# 03_Template_Indication.net
KiCad netlist of a schematic drawn in Altium Designer
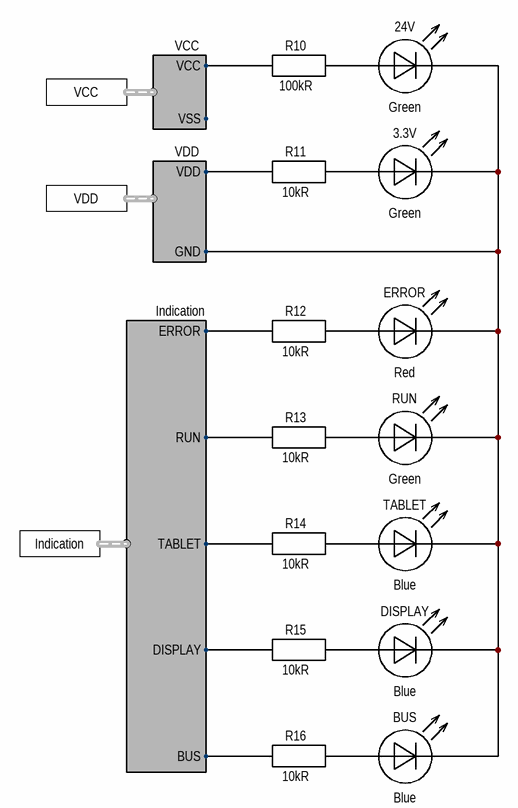
[diagram p0: 03.Template_Indication.SchDoc]

(export (version "E")
  (design (tool "Eeschema 10.0.6"))
  (components
    (comp (ref "3.3V")
      (value "Green")
      (footprint "LED2012N")
      (description "Led Indication Green 2012")
      (fields (field (name "MANUFACTURER") "XINGLIGHT"))
      (libsource (lib "Discrete_LED_Indication_SMD_GOST") (part "LED_Color_A"))
    )
    (comp (ref "24V")
      (value "Green")
      (footprint "LED2012N")
      (description "Led Indication Green 2012")
      (fields (field (name "MANUFACTURER") "XINGLIGHT"))
      (libsource (lib "Discrete_LED_Indication_SMD_GOST") (part "LED_Color_A"))
    )
    (comp (ref "BUS")
      (value "Blue")
      (footprint "LED2012N")
      (description "Led Indication Blue 2012")
      (fields (field (name "MANUFACTURER") "XINGLIGHT"))
      (libsource (lib "Discrete_LED_Indication_SMD_GOST") (part "LED_Color_A"))
    )
    (comp (ref "DISPLAY")
      (value "Blue")
      (footprint "LED2012N")
      (description "Led Indication Blue 2012")
      (fields (field (name "MANUFACTURER") "XINGLIGHT"))
      (libsource (lib "Discrete_LED_Indication_SMD_GOST") (part "LED_Color_A"))
    )
    (comp (ref "ERROR")
      (value "Red")
      (footprint "LED2012N")
      (description "Led Indication Red 2012")
      (fields (field (name "MANUFACTURER") "XINGLIGHT"))
      (libsource (lib "Discrete_LED_Indication_SMD_GOST") (part "LED_Color_A"))
    )
    (comp (ref "R10")
      (value "100kR")
      (footprint "RESC2012N")
      (description "Resistor Ceramic 100kR 1% 2012")
      (fields (field (name "MANUFACTURER") "UNI-ROYAL") (field (name "TOLERANCE") "±1%"))
      (libsource (lib "Discrete_Resistors_Ceramic_2012_1%_SMD_GOST") (part "Resistor_A"))
    )
    (comp (ref "R11")
      (value "10kR")
      (footprint "RESC2012N")
      (description "Resistor Ceramic 10kR 1% 2012")
      (fields (field (name "MANUFACTURER") "UNI-ROYAL") (field (name "TOLERANCE") "±1%"))
      (libsource (lib "Discrete_Resistors_Ceramic_2012_1%_SMD_GOST") (part "Resistor_A"))
    )
    (comp (ref "R12")
      (value "10kR")
      (footprint "RESC2012N")
      (description "Resistor Ceramic 10kR 1% 2012")
      (fields (field (name "MANUFACTURER") "UNI-ROYAL") (field (name "TOLERANCE") "±1%"))
      (libsource (lib "Discrete_Resistors_Ceramic_2012_1%_SMD_GOST") (part "Resistor_A"))
    )
    (comp (ref "R13")
      (value "10kR")
      (footprint "RESC2012N")
      (description "Resistor Ceramic 10kR 1% 2012")
      (fields (field (name "MANUFACTURER") "UNI-ROYAL") (field (name "TOLERANCE") "±1%"))
      (libsource (lib "Discrete_Resistors_Ceramic_2012_1%_SMD_GOST") (part "Resistor_A"))
    )
    (comp (ref "R14")
      (value "10kR")
      (footprint "RESC2012N")
      (description "Resistor Ceramic 10kR 1% 2012")
      (fields (field (name "MANUFACTURER") "UNI-ROYAL") (field (name "TOLERANCE") "±1%"))
      (libsource (lib "Discrete_Resistors_Ceramic_2012_1%_SMD_GOST") (part "Resistor_A"))
    )
    (comp (ref "R15")
      (value "10kR")
      (footprint "RESC2012N")
      (description "Resistor Ceramic 10kR 1% 2012")
      (fields (field (name "MANUFACTURER") "UNI-ROYAL") (field (name "TOLERANCE") "±1%"))
      (libsource (lib "Discrete_Resistors_Ceramic_2012_1%_SMD_GOST") (part "Resistor_A"))
    )
    (comp (ref "R16")
      (value "10kR")
      (footprint "RESC2012N")
      (description "Resistor Ceramic 10kR 1% 2012")
      (fields (field (name "MANUFACTURER") "UNI-ROYAL") (field (name "TOLERANCE") "±1%"))
      (libsource (lib "Discrete_Resistors_Ceramic_2012_1%_SMD_GOST") (part "Resistor_A"))
    )
    (comp (ref "RUN")
      (value "Green")
      (footprint "LED2012N")
      (description "Led Indication Green 2012")
      (fields (field (name "MANUFACTURER") "XINGLIGHT"))
      (libsource (lib "Discrete_LED_Indication_SMD_GOST") (part "LED_Color_A"))
    )
    (comp (ref "TABLET")
      (value "Blue")
      (footprint "LED2012N")
      (description "Led Indication Blue 2012")
      (fields (field (name "MANUFACTURER") "XINGLIGHT"))
      (libsource (lib "Discrete_LED_Indication_SMD_GOST") (part "LED_Color_A"))
    )
  )
  (nets
    (net (code "4") (name "/BUS") (class "Default")
      (node (ref "R16") (pin "1") (pinfunction "1_1") (pintype "passive"))
    )
    (net (code "5") (name "/DISPLAY") (class "Default")
      (node (ref "R15") (pin "1") (pinfunction "1_1") (pintype "passive"))
    )
    (net (code "6") (name "/ERROR") (class "Default")
      (node (ref "R12") (pin "1") (pinfunction "1_1") (pintype "passive"))
    )
    (net (code "7") (name "/GND") (class "Default")
      (node (ref "24V") (pin "1") (pinfunction "1_1") (pintype "passive"))
      (node (ref "3.3V") (pin "1") (pinfunction "1_1") (pintype "passive"))
      (node (ref "BUS") (pin "1") (pinfunction "1_1") (pintype "passive"))
      (node (ref "DISPLAY") (pin "1") (pinfunction "1_1") (pintype "passive"))
      (node (ref "ERROR") (pin "1") (pinfunction "1_1") (pintype "passive"))
      (node (ref "RUN") (pin "1") (pinfunction "1_1") (pintype "passive"))
      (node (ref "TABLET") (pin "1") (pinfunction "1_1") (pintype "passive"))
    )
    (net (code "8") (name "/RUN") (class "Default")
      (node (ref "R13") (pin "1") (pinfunction "1_1") (pintype "passive"))
    )
    (net (code "9") (name "/TABLET") (class "Default")
      (node (ref "R14") (pin "1") (pinfunction "1_1") (pintype "passive"))
    )
    (net (code "13") (name "Net-(3.3V-Pad2)") (class "Default")
      (node (ref "3.3V") (pin "2") (pinfunction "2_2") (pintype "passive"))
      (node (ref "R11") (pin "2") (pinfunction "2_2") (pintype "passive"))
    )
    (net (code "14") (name "Net-(24V-Pad2)") (class "Default")
      (node (ref "24V") (pin "2") (pinfunction "2_2") (pintype "passive"))
      (node (ref "R10") (pin "2") (pinfunction "2_2") (pintype "passive"))
    )
    (net (code "15") (name "Net-(BUS-Pad2)") (class "Default")
      (node (ref "BUS") (pin "2") (pinfunction "2_2") (pintype "passive"))
      (node (ref "R16") (pin "2") (pinfunction "2_2") (pintype "passive"))
    )
    (net (code "16") (name "Net-(DISPLAY-Pad2)") (class "Default")
      (node (ref "DISPLAY") (pin "2") (pinfunction "2_2") (pintype "passive"))
      (node (ref "R15") (pin "2") (pinfunction "2_2") (pintype "passive"))
    )
    (net (code "17") (name "Net-(ERROR-Pad2)") (class "Default")
      (node (ref "ERROR") (pin "2") (pinfunction "2_2") (pintype "passive"))
      (node (ref "R12") (pin "2") (pinfunction "2_2") (pintype "passive"))
    )
    (net (code "18") (name "Net-(R13-Pad2)") (class "Default")
      (node (ref "R13") (pin "2") (pinfunction "2_2") (pintype "passive"))
      (node (ref "RUN") (pin "2") (pinfunction "2_2") (pintype "passive"))
    )
    (net (code "19") (name "Net-(R14-Pad2)") (class "Default")
      (node (ref "R14") (pin "2") (pinfunction "2_2") (pintype "passive"))
      (node (ref "TABLET") (pin "2") (pinfunction "2_2") (pintype "passive"))
    )
    (net (code "20") (name "unconnected-(R10-Pad1)") (class "Default")
      (node (ref "R10") (pin "1") (pinfunction "1_1") (pintype "passive"))
    )
    (net (code "21") (name "unconnected-(R11-Pad1)") (class "Default")
      (node (ref "R11") (pin "1") (pinfunction "1_1") (pintype "passive"))
    )
  )
)
